# design.net
KiCad netlist of a schematic drawn in Altium Designer
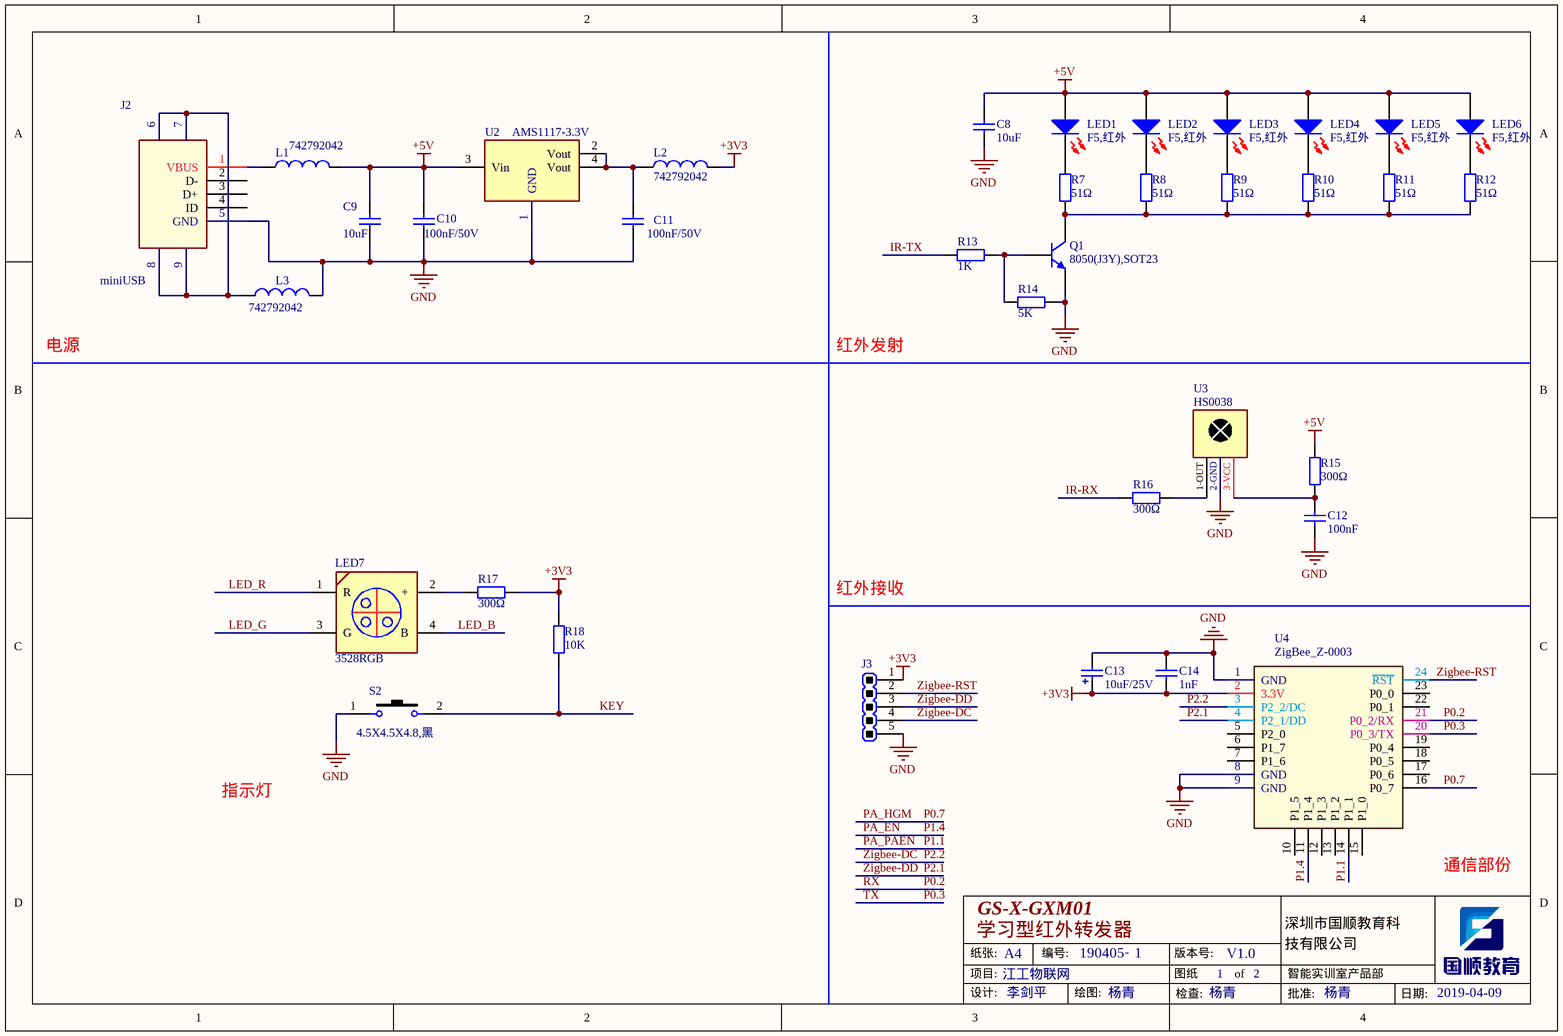
[diagram p0: 学习型红外转发器.SchDoc]

(export (version "E")
  (design (tool "Eeschema 10.0.6"))
  (components
    (comp (ref "C8")
      (value "10uF")
      (footprint "C0603")
      (description "Capacitor")
      (libsource (lib "贴片电容") (part "10uF_16V_0603"))
    )
    (comp (ref "C9")
      (value "10uF")
      (footprint "C0603")
      (description "Capacitor")
      (libsource (lib "贴片电容") (part "10uF_16V_0603"))
    )
    (comp (ref "C10")
      (value "100nF/50V")
      (footprint "C0603")
      (description "Capacitor")
      (libsource (lib "贴片电容") (part "100nF_50V_0603"))
    )
    (comp (ref "C11")
      (value "100nF/50V")
      (footprint "C0603")
      (description "Capacitor")
      (libsource (lib "贴片电容") (part "100nF_50V_0603"))
    )
    (comp (ref "C12")
      (value "100nF")
      (footprint "C0603")
      (description "Capacitor")
      (libsource (lib "贴片电容") (part "100nF_50V_0603"))
    )
    (comp (ref "C13")
      (value "10uF/25V")
      (footprint "TC3528X21B")
      (description "钽电容,10uF/25V-3528B")
      (libsource (lib "贴片电容") (part "CAPC-10uF/25V_3528B"))
    )
    (comp (ref "C14")
      (value "1nF")
      (footprint "C0603")
      (description "Capacitor")
      (libsource (lib "贴片电容") (part "1nF_50V_0603"))
    )
    (comp (ref "J2")
      (value "miniUSB")
      (footprint "USB mini/SM0.8-6H5")
      (description "mini-USB 5PF USB 母座")
      (libsource (lib "接口") (part "USB-mini-5PF"))
    )
    (comp (ref "J3")
      (value "HDRM-1*5-2.54-AK")
      (footprint "HDRM-2.54-1*5P-AK1")
      (description "排针,直")
      (libsource (lib "接口") (part "HDRM-1*5-2.54-AK"))
    )
    (comp (ref "L1")
      (value "742792042")
      (footprint "L0805")
      (description "WE-CBF,600@100M,500Ohm,200mA,0805,742792042")
      (libsource (lib "电感") (part "BEAD-742792042_0805"))
    )
    (comp (ref "L2")
      (value "742792042")
      (footprint "L0805")
      (description "WE-CBF,600@100M,500Ohm,200mA,0805,742792042")
      (libsource (lib "电感") (part "BEAD-742792042_0805"))
    )
    (comp (ref "L3")
      (value "742792042")
      (footprint "L0805")
      (description "WE-CBF,600@100M,500Ohm,200mA,0805,742792042")
      (libsource (lib "电感") (part "BEAD-742792042_0805"))
    )
    (comp (ref "LED1")
      (value "F5,红外")
      (footprint "IR-F5-V")
      (description "红外发射")
      (libsource (lib "二极管") (part "LED-IR_F5"))
    )
    (comp (ref "LED2")
      (value "F5,红外")
      (footprint "IR-F5-V")
      (description "红外发射")
      (libsource (lib "二极管") (part "LED-IR_F5"))
    )
    (comp (ref "LED3")
      (value "F5,红外")
      (footprint "IR-F5-V")
      (description "红外发射")
      (libsource (lib "二极管") (part "LED-IR_F5"))
    )
    (comp (ref "LED4")
      (value "F5,红外")
      (footprint "IR-F5-V")
      (description "红外发射")
      (libsource (lib "二极管") (part "LED-IR_F5"))
    )
    (comp (ref "LED5")
      (value "F5,红外")
      (footprint "IR-F5-V")
      (description "红外发射")
      (libsource (lib "二极管") (part "LED-IR_F5"))
    )
    (comp (ref "LED6")
      (value "F5,红外")
      (footprint "IR-F5-V")
      (description "红外发射")
      (libsource (lib "二极管") (part "LED-IR_F5"))
    )
    (comp (ref "LED7")
      (value "3528RGB")
      (footprint "LED_3528RGB")
      (description "3528,LED RGB")
      (libsource (lib "二极管") (part "RGB_3528"))
    )
    (comp (ref "Q1")
      (value "8050(J3Y),SOT23")
      (footprint "SOT23")
      (description "NPN,8050,SOT23")
      (libsource (lib "三极管") (part "NPN_8050(J3Y)_SOT23"))
    )
    (comp (ref "R7")
      (value "51Ω")
      (footprint "R0603")
      (description "51Ω,±5%,0603")
      (libsource (lib "贴片电阻") (part "51Ω_5%_0603"))
    )
    (comp (ref "R8")
      (value "51Ω")
      (footprint "R0603")
      (description "51Ω,±5%,0603")
      (libsource (lib "贴片电阻") (part "51Ω_5%_0603"))
    )
    (comp (ref "R9")
      (value "51Ω")
      (footprint "R0603")
      (description "51Ω,±5%,0603")
      (libsource (lib "贴片电阻") (part "51Ω_5%_0603"))
    )
    (comp (ref "R10")
      (value "51Ω")
      (footprint "R0603")
      (description "51Ω,±5%,0603")
      (libsource (lib "贴片电阻") (part "51Ω_5%_0603"))
    )
    (comp (ref "R11")
      (value "51Ω")
      (footprint "R0603")
      (description "51Ω,±5%,0603")
      (libsource (lib "贴片电阻") (part "51Ω_5%_0603"))
    )
    (comp (ref "R12")
      (value "51Ω")
      (footprint "R0603")
      (description "51Ω,±5%,0603")
      (libsource (lib "贴片电阻") (part "51Ω_5%_0603"))
    )
    (comp (ref "R13")
      (value "1K")
      (footprint "R0603")
      (description "1K,±5%,0603")
      (libsource (lib "贴片电阻") (part "1K_5%_0603"))
    )
    (comp (ref "R14")
      (value "5K")
      (footprint "R0603")
      (description "5K,±5%,0603")
      (libsource (lib "贴片电阻") (part "5K_5%_0603"))
    )
    (comp (ref "R15")
      (value "300Ω")
      (footprint "R0603")
      (description "300Ω,±5%,0603")
      (libsource (lib "") (part "300Ω_5%_0603_2"))
    )
    (comp (ref "R16")
      (value "300Ω")
      (footprint "R0603")
      (description "300Ω,±5%,0603")
      (libsource (lib "") (part "300Ω_5%_0603_1"))
    )
    (comp (ref "R17")
      (value "300Ω")
      (footprint "R0603")
      (description "300Ω,±5%,0603")
      (libsource (lib "贴片电阻") (part "300Ω_5%_0603"))
    )
    (comp (ref "R18")
      (value "10K")
      (footprint "R0603")
      (description "10K,±5%,0603")
      (libsource (lib "贴片电阻") (part "10K_5%_0603"))
    )
    (comp (ref "S2")
      (value "4.5X4.5X4.8,黑")
      (footprint "SW2-4.5*4.5*4.8MM-Side-BK")
      (description "4.5X4.5X4.8,侧按3P,黑")
      (libsource (lib "按键开关") (part "SW-PB_4.5X4.5X4.8-3P-SIDE-BK"))
    )
    (comp (ref "U2")
      (value "AMS1117-3.3V")
      (footprint "SOT-223")
      (description "三端稳压器")
      (libsource (lib "IC") (part "AMS1117-3.3V_SOT223"))
    )
    (comp (ref "U3")
      (value "HS0038")
      (footprint "HS0038-H")
      (description "一体红外接收头")
      (libsource (lib "传感器") (part "HS0038"))
    )
    (comp (ref "U4")
      (value "ZigBee_Z-0003")
      (footprint "Module_ZigBee_Z-0003")
      (description "zigbee模块")
      (libsource (lib "杂项元件") (part "Module_ZigBee_Z-0003"))
    )
  )
  (nets
    (net (code "1") (name "+3V3") (class "Default")
      (node (ref "C13") (pin "1") (pinfunction "1_1") (pintype "passive"))
      (node (ref "C14") (pin "1") (pinfunction "1_1") (pintype "passive"))
      (node (ref "J3") (pin "1") (pinfunction "1_1") (pintype "passive"))
      (node (ref "L2") (pin "2") (pinfunction "2_2") (pintype "passive"))
      (node (ref "R17") (pin "1") (pinfunction "1_1") (pintype "passive"))
      (node (ref "R18") (pin "1") (pinfunction "1_1") (pintype "passive"))
      (node (ref "U4") (pin "2") (pinfunction "3.3V_2") (pintype "passive"))
    )
    (net (code "2") (name "+5V") (class "Default")
      (node (ref "C10") (pin "1") (pinfunction "1_1") (pintype "passive"))
      (node (ref "C8") (pin "1") (pinfunction "1_1") (pintype "passive"))
      (node (ref "C9") (pin "1") (pinfunction "1_1") (pintype "passive"))
      (node (ref "L1") (pin "2") (pinfunction "2_2") (pintype "passive"))
      (node (ref "LED1") (pin "1") (pinfunction "A_1") (pintype "passive"))
      (node (ref "LED2") (pin "1") (pinfunction "A_1") (pintype "passive"))
      (node (ref "LED3") (pin "1") (pinfunction "A_1") (pintype "passive"))
      (node (ref "LED4") (pin "1") (pinfunction "A_1") (pintype "passive"))
      (node (ref "LED5") (pin "1") (pinfunction "A_1") (pintype "passive"))
      (node (ref "LED6") (pin "1") (pinfunction "A_1") (pintype "passive"))
      (node (ref "R15") (pin "2") (pinfunction "2_2") (pintype "passive"))
      (node (ref "U2") (pin "3") (pinfunction "Vin_3") (pintype "passive"))
    )
    (net (code "3") (name "/IR-RX") (class "Default")
      (node (ref "R16") (pin "1") (pinfunction "1_1") (pintype "passive"))
    )
    (net (code "4") (name "/IR-TX") (class "Default")
      (node (ref "R13") (pin "1") (pinfunction "1_1") (pintype "passive"))
    )
    (net (code "5") (name "/KEY") (class "Default")
      (node (ref "R18") (pin "2") (pinfunction "2_2") (pintype "passive"))
      (node (ref "S2") (pin "2") (pinfunction "2_2") (pintype "passive"))
    )
    (net (code "6") (name "/LED_B") (class "Default")
      (node (ref "LED7") (pin "4") (pinfunction "B_4") (pintype "passive"))
    )
    (net (code "7") (name "/LED_G") (class "Default")
      (node (ref "LED7") (pin "3") (pinfunction "G_3") (pintype "passive"))
    )
    (net (code "8") (name "/LED_R") (class "Default")
      (node (ref "LED7") (pin "1") (pinfunction "R_1") (pintype "passive"))
    )
    (net (code "9") (name "/P0.2") (class "Default")
      (node (ref "U4") (pin "21") (pinfunction "P0_2/RX_21") (pintype "passive"))
    )
    (net (code "10") (name "/P0.3") (class "Default")
      (node (ref "U4") (pin "20") (pinfunction "P0_3/TX_20") (pintype "passive"))
    )
    (net (code "11") (name "/P0.7") (class "Default")
      (node (ref "U4") (pin "16") (pinfunction "P0_7_16") (pintype "passive"))
    )
    (net (code "12") (name "/P1.1") (class "Default")
      (node (ref "U4") (pin "14") (pinfunction "P1_1_14") (pintype "passive"))
    )
    (net (code "13") (name "/P1.4") (class "Default")
      (node (ref "U4") (pin "11") (pinfunction "P1_4_11") (pintype "passive"))
    )
    (net (code "14") (name "/P2.1") (class "Default")
      (node (ref "J3") (pin "3") (pinfunction "3_3") (pintype "passive"))
      (node (ref "U4") (pin "4") (pinfunction "P2_1/DD_4") (pintype "passive"))
    )
    (net (code "15") (name "/P2.2") (class "Default")
      (node (ref "J3") (pin "4") (pinfunction "4_4") (pintype "passive"))
      (node (ref "U4") (pin "3") (pinfunction "P2_2/DC_3") (pintype "passive"))
    )
    (net (code "16") (name "/Zigbee-RST") (class "Default")
      (node (ref "J3") (pin "2") (pinfunction "2_2") (pintype "passive"))
      (node (ref "U4") (pin "24") (pinfunction "~{RST}_24") (pintype "passive"))
    )
    (net (code "17") (name "GND") (class "Default")
      (node (ref "C10") (pin "2") (pinfunction "2_2") (pintype "passive"))
      (node (ref "C11") (pin "2") (pinfunction "2_2") (pintype "passive"))
      (node (ref "C12") (pin "2") (pinfunction "2_2") (pintype "passive"))
      (node (ref "C13") (pin "2") (pinfunction "2_2") (pintype "passive"))
      (node (ref "C14") (pin "2") (pinfunction "2_2") (pintype "passive"))
      (node (ref "C8") (pin "2") (pinfunction "2_2") (pintype "passive"))
      (node (ref "C9") (pin "2") (pinfunction "2_2") (pintype "passive"))
      (node (ref "J2") (pin "5") (pinfunction "GND_5") (pintype "passive"))
      (node (ref "J3") (pin "5") (pinfunction "5_5") (pintype "passive"))
      (node (ref "L3") (pin "2") (pinfunction "2_2") (pintype "passive"))
      (node (ref "Q1") (pin "2") (pinfunction "E_2") (pintype "passive"))
      (node (ref "R14") (pin "2") (pinfunction "2_2") (pintype "passive"))
      (node (ref "S2") (pin "1") (pinfunction "1_1") (pintype "passive"))
      (node (ref "U2") (pin "1") (pinfunction "GND_1") (pintype "passive"))
      (node (ref "U3") (pin "2") (pinfunction "GND_2") (pintype "passive"))
      (node (ref "U4") (pin "1") (pinfunction "GND_1") (pintype "passive"))
      (node (ref "U4") (pin "8") (pinfunction "GND_8") (pintype "passive"))
      (node (ref "U4") (pin "9") (pinfunction "GND_9") (pintype "passive"))
    )
    (net (code "18") (name "Net-(C11-Pad1)") (class "Default")
      (node (ref "C11") (pin "1") (pinfunction "1_1") (pintype "passive"))
      (node (ref "L2") (pin "1") (pinfunction "1_1") (pintype "passive"))
      (node (ref "U2") (pin "2") (pinfunction "Vout_2") (pintype "passive"))
      (node (ref "U2") (pin "4") (pinfunction "Vout_4") (pintype "passive"))
    )
    (net (code "19") (name "Net-(J2-Pad6)") (class "Default")
      (node (ref "J2") (pin "6") (pinfunction "6_6") (pintype "passive"))
      (node (ref "J2") (pin "7") (pinfunction "7_7") (pintype "passive"))
      (node (ref "J2") (pin "8") (pinfunction "8_8") (pintype "passive"))
      (node (ref "J2") (pin "9") (pinfunction "9_9") (pintype "passive"))
      (node (ref "L3") (pin "1") (pinfunction "1_1") (pintype "passive"))
    )
    (net (code "20") (name "Net-(J2-VBUS)") (class "Default")
      (node (ref "J2") (pin "1") (pinfunction "VBUS_1") (pintype "passive"))
      (node (ref "L1") (pin "1") (pinfunction "1_1") (pintype "passive"))
    )
    (net (code "21") (name "Net-(LED1-K)") (class "Default")
      (node (ref "LED1") (pin "2") (pinfunction "K_2") (pintype "passive"))
      (node (ref "R7") (pin "2") (pinfunction "2_2") (pintype "passive"))
    )
    (net (code "22") (name "Net-(LED2-K)") (class "Default")
      (node (ref "LED2") (pin "2") (pinfunction "K_2") (pintype "passive"))
      (node (ref "R8") (pin "2") (pinfunction "2_2") (pintype "passive"))
    )
    (net (code "23") (name "Net-(LED3-K)") (class "Default")
      (node (ref "LED3") (pin "2") (pinfunction "K_2") (pintype "passive"))
      (node (ref "R9") (pin "2") (pinfunction "2_2") (pintype "passive"))
    )
    (net (code "24") (name "Net-(LED4-K)") (class "Default")
      (node (ref "LED4") (pin "2") (pinfunction "K_2") (pintype "passive"))
      (node (ref "R10") (pin "2") (pinfunction "2_2") (pintype "passive"))
    )
    (net (code "25") (name "Net-(LED5-K)") (class "Default")
      (node (ref "LED5") (pin "2") (pinfunction "K_2") (pintype "passive"))
      (node (ref "R11") (pin "2") (pinfunction "2_2") (pintype "passive"))
    )
    (net (code "26") (name "Net-(LED6-K)") (class "Default")
      (node (ref "LED6") (pin "2") (pinfunction "K_2") (pintype "passive"))
      (node (ref "R12") (pin "2") (pinfunction "2_2") (pintype "passive"))
    )
    (net (code "27") (name "Net-(LED7-+)") (class "Default")
      (node (ref "LED7") (pin "2") (pinfunction "+_2") (pintype "passive"))
      (node (ref "R17") (pin "2") (pinfunction "2_2") (pintype "passive"))
    )
    (net (code "28") (name "Net-(Q1-B)") (class "Default")
      (node (ref "Q1") (pin "1") (pinfunction "B_1") (pintype "passive"))
      (node (ref "R13") (pin "2") (pinfunction "2_2") (pintype "passive"))
      (node (ref "R14") (pin "1") (pinfunction "1_1") (pintype "passive"))
    )
    (net (code "29") (name "Net-(Q1-C)") (class "Default")
      (node (ref "Q1") (pin "3") (pinfunction "C_3") (pintype "passive"))
      (node (ref "R10") (pin "1") (pinfunction "1_1") (pintype "passive"))
      (node (ref "R11") (pin "1") (pinfunction "1_1") (pintype "passive"))
      (node (ref "R12") (pin "1") (pinfunction "1_1") (pintype "passive"))
      (node (ref "R7") (pin "1") (pinfunction "1_1") (pintype "passive"))
      (node (ref "R8") (pin "1") (pinfunction "1_1") (pintype "passive"))
      (node (ref "R9") (pin "1") (pinfunction "1_1") (pintype "passive"))
    )
    (net (code "30") (name "Net-(U3-VCC)") (class "Default")
      (node (ref "C12") (pin "1") (pinfunction "1_1") (pintype "passive"))
      (node (ref "R15") (pin "1") (pinfunction "1_1") (pintype "passive"))
      (node (ref "U3") (pin "3") (pinfunction "VCC_3") (pintype "passive"))
    )
    (net (code "31") (name "Net-(U3-out)") (class "Default")
      (node (ref "R16") (pin "2") (pinfunction "2_2") (pintype "passive"))
      (node (ref "U3") (pin "1") (pinfunction "out_1") (pintype "passive"))
    )
    (net (code "32") (name "unconnected-(J2-D+-Pad3)") (class "Default")
      (node (ref "J2") (pin "3") (pinfunction "D+_3") (pintype "passive"))
    )
    (net (code "33") (name "unconnected-(J2-D--Pad2)") (class "Default")
      (node (ref "J2") (pin "2") (pinfunction "D-_2") (pintype "passive"))
    )
    (net (code "34") (name "unconnected-(J2-ID-Pad4)") (class "Default")
      (node (ref "J2") (pin "4") (pinfunction "ID_4") (pintype "passive"))
    )
    (net (code "35") (name "unconnected-(U4-P0_0-Pad23)") (class "Default")
      (node (ref "U4") (pin "23") (pinfunction "P0_0_23") (pintype "passive"))
    )
    (net (code "36") (name "unconnected-(U4-P0_1-Pad22)") (class "Default")
      (node (ref "U4") (pin "22") (pinfunction "P0_1_22") (pintype "passive"))
    )
    (net (code "37") (name "unconnected-(U4-P0_4-Pad19)") (class "Default")
      (node (ref "U4") (pin "19") (pinfunction "P0_4_19") (pintype "passive"))
    )
    (net (code "38") (name "unconnected-(U4-P0_5-Pad18)") (class "Default")
      (node (ref "U4") (pin "18") (pinfunction "P0_5_18") (pintype "passive"))
    )
    (net (code "39") (name "unconnected-(U4-P0_6-Pad17)") (class "Default")
      (node (ref "U4") (pin "17") (pinfunction "P0_6_17") (pintype "passive"))
    )
    (net (code "40") (name "unconnected-(U4-P1_0-Pad15)") (class "Default")
      (node (ref "U4") (pin "15") (pinfunction "P1_0_15") (pintype "passive"))
    )
    (net (code "41") (name "unconnected-(U4-P1_2-Pad13)") (class "Default")
      (node (ref "U4") (pin "13") (pinfunction "P1_2_13") (pintype "passive"))
    )
    (net (code "42") (name "unconnected-(U4-P1_3-Pad12)") (class "Default")
      (node (ref "U4") (pin "12") (pinfunction "P1_3_12") (pintype "passive"))
    )
    (net (code "43") (name "unconnected-(U4-P1_5-Pad10)") (class "Default")
      (node (ref "U4") (pin "10") (pinfunction "P1_5_10") (pintype "passive"))
    )
    (net (code "44") (name "unconnected-(U4-P1_6-Pad7)") (class "Default")
      (node (ref "U4") (pin "7") (pinfunction "P1_6_7") (pintype "passive"))
    )
    (net (code "45") (name "unconnected-(U4-P1_7-Pad6)") (class "Default")
      (node (ref "U4") (pin "6") (pinfunction "P1_7_6") (pintype "passive"))
    )
    (net (code "46") (name "unconnected-(U4-P2_0-Pad5)") (class "Default")
      (node (ref "U4") (pin "5") (pinfunction "P2_0_5") (pintype "passive"))
    )
  )
)
